# ProgrammersKeyboard_Keyboard_Schematic.net
KiCad netlist of a schematic drawn in EAGLE
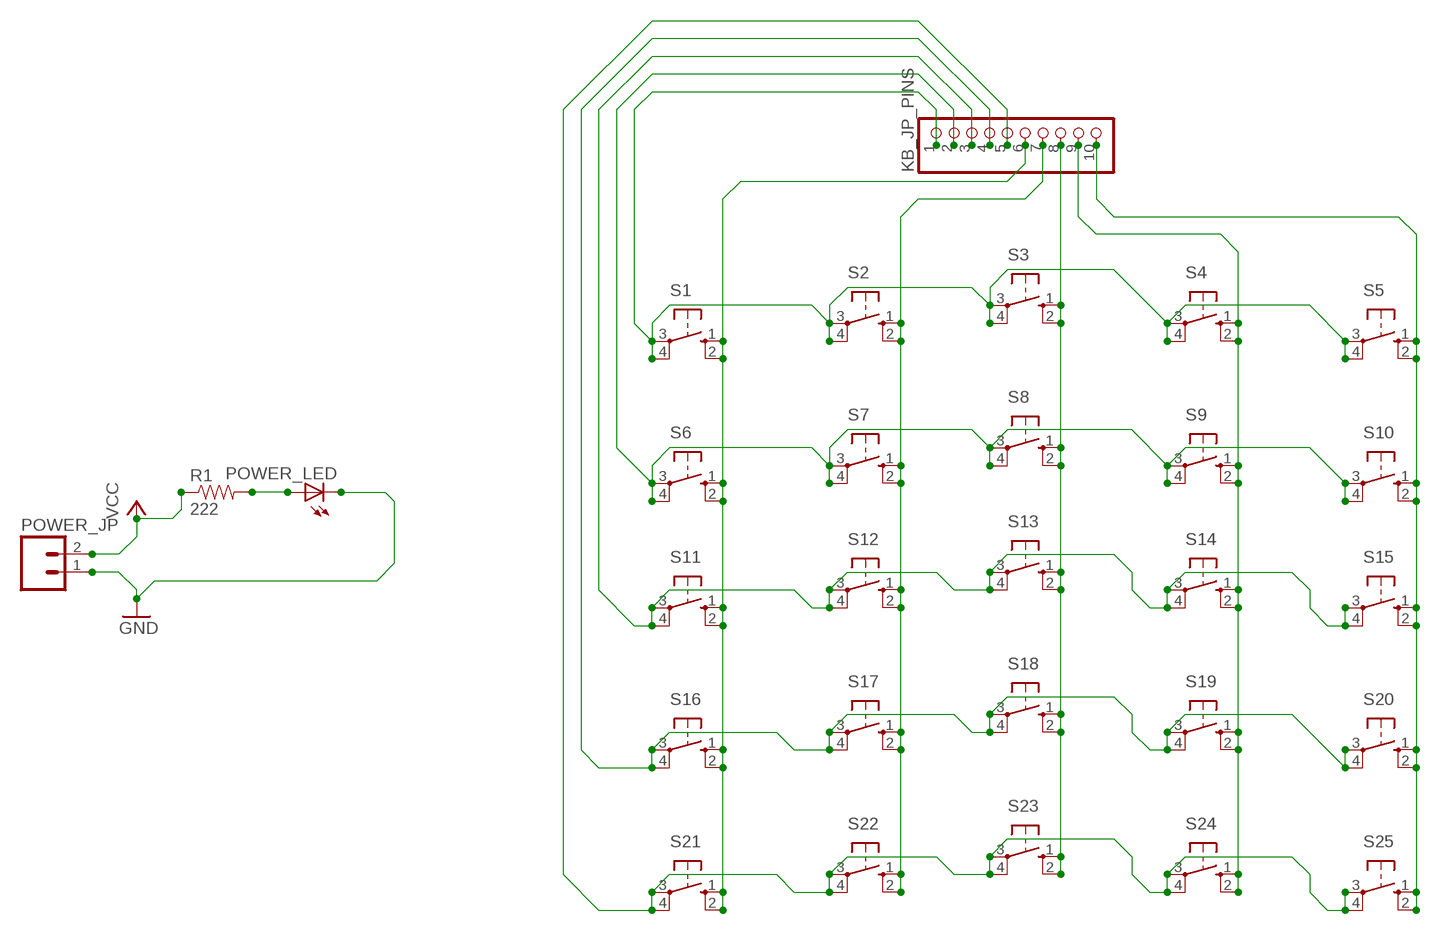
[diagram p0: schematic, sheet 1]

(export (version "E")
  (design (tool "Eeschema 10.0.6"))
  (components
    (comp (ref "KB_JP_PINS")
      (value "PINHD-1X10/90")
      (footprint "eagle-import:1X10_90")
      (libsource (lib "eagle-import") (part "PINHD-1X10/90"))
    )
    (comp (ref "POWER_JP")
      (value "M02PTH3")
      (footprint "eagle-import:1X02_LONGPADS")
      (libsource (lib "eagle-import") (part "M02PTH3"))
    )
    (comp (ref "POWER_LED")
      (value "LEDSMT1206")
      (footprint "eagle-import:1206")
      (libsource (lib "eagle-import") (part "LEDSMT1206"))
    )
    (comp (ref "R1")
      (value "222")
      (footprint "eagle-import:1206")
      (libsource (lib "eagle-import") (part "RESISTOR1206"))
    )
    (comp (ref "S1")
      (value "10-XX")
      (footprint "eagle-import:B3F-10XX")
      (fields (field (name "MPN") "B3F-1000"))
      (libsource (lib "eagle-import") (part "10-XX"))
    )
    (comp (ref "S2")
      (value "10-XX")
      (footprint "eagle-import:B3F-10XX")
      (fields (field (name "MPN") "B3F-1000"))
      (libsource (lib "eagle-import") (part "10-XX"))
    )
    (comp (ref "S3")
      (value "10-XX")
      (footprint "eagle-import:B3F-10XX")
      (fields (field (name "MPN") "B3F-1000"))
      (libsource (lib "eagle-import") (part "10-XX"))
    )
    (comp (ref "S4")
      (value "10-XX")
      (footprint "eagle-import:B3F-10XX")
      (fields (field (name "MPN") "B3F-1000"))
      (libsource (lib "eagle-import") (part "10-XX"))
    )
    (comp (ref "S5")
      (value "10-XX")
      (footprint "eagle-import:B3F-10XX")
      (fields (field (name "MPN") "B3F-1000"))
      (libsource (lib "eagle-import") (part "10-XX"))
    )
    (comp (ref "S6")
      (value "10-XX")
      (footprint "eagle-import:B3F-10XX")
      (fields (field (name "MPN") "B3F-1000"))
      (libsource (lib "eagle-import") (part "10-XX"))
    )
    (comp (ref "S7")
      (value "10-XX")
      (footprint "eagle-import:B3F-10XX")
      (fields (field (name "MPN") "B3F-1000"))
      (libsource (lib "eagle-import") (part "10-XX"))
    )
    (comp (ref "S8")
      (value "10-XX")
      (footprint "eagle-import:B3F-10XX")
      (fields (field (name "MPN") "B3F-1000"))
      (libsource (lib "eagle-import") (part "10-XX"))
    )
    (comp (ref "S9")
      (value "10-XX")
      (footprint "eagle-import:B3F-10XX")
      (fields (field (name "MPN") "B3F-1000"))
      (libsource (lib "eagle-import") (part "10-XX"))
    )
    (comp (ref "S10")
      (value "10-XX")
      (footprint "eagle-import:B3F-10XX")
      (fields (field (name "MPN") "B3F-1000"))
      (libsource (lib "eagle-import") (part "10-XX"))
    )
    (comp (ref "S11")
      (value "10-XX")
      (footprint "eagle-import:B3F-10XX")
      (fields (field (name "MPN") "B3F-1000"))
      (libsource (lib "eagle-import") (part "10-XX"))
    )
    (comp (ref "S12")
      (value "10-XX")
      (footprint "eagle-import:B3F-10XX")
      (fields (field (name "MPN") "B3F-1000"))
      (libsource (lib "eagle-import") (part "10-XX"))
    )
    (comp (ref "S13")
      (value "10-XX")
      (footprint "eagle-import:B3F-10XX")
      (fields (field (name "MPN") "B3F-1000"))
      (libsource (lib "eagle-import") (part "10-XX"))
    )
    (comp (ref "S14")
      (value "10-XX")
      (footprint "eagle-import:B3F-10XX")
      (fields (field (name "MPN") "B3F-1000"))
      (libsource (lib "eagle-import") (part "10-XX"))
    )
    (comp (ref "S15")
      (value "10-XX")
      (footprint "eagle-import:B3F-10XX")
      (fields (field (name "MPN") "B3F-1000"))
      (libsource (lib "eagle-import") (part "10-XX"))
    )
    (comp (ref "S16")
      (value "10-XX")
      (footprint "eagle-import:B3F-10XX")
      (fields (field (name "MPN") "B3F-1000"))
      (libsource (lib "eagle-import") (part "10-XX"))
    )
    (comp (ref "S17")
      (value "10-XX")
      (footprint "eagle-import:B3F-10XX")
      (fields (field (name "MPN") "B3F-1000"))
      (libsource (lib "eagle-import") (part "10-XX"))
    )
    (comp (ref "S18")
      (value "10-XX")
      (footprint "eagle-import:B3F-10XX")
      (fields (field (name "MPN") "B3F-1000"))
      (libsource (lib "eagle-import") (part "10-XX"))
    )
    (comp (ref "S19")
      (value "10-XX")
      (footprint "eagle-import:B3F-10XX")
      (fields (field (name "MPN") "B3F-1000"))
      (libsource (lib "eagle-import") (part "10-XX"))
    )
    (comp (ref "S20")
      (value "10-XX")
      (footprint "eagle-import:B3F-10XX")
      (fields (field (name "MPN") "B3F-1000"))
      (libsource (lib "eagle-import") (part "10-XX"))
    )
    (comp (ref "S21")
      (value "10-XX")
      (footprint "eagle-import:B3F-10XX")
      (fields (field (name "MPN") "B3F-1000"))
      (libsource (lib "eagle-import") (part "10-XX"))
    )
    (comp (ref "S22")
      (value "10-XX")
      (footprint "eagle-import:B3F-10XX")
      (fields (field (name "MPN") "B3F-1000"))
      (libsource (lib "eagle-import") (part "10-XX"))
    )
    (comp (ref "S23")
      (value "10-XX")
      (footprint "eagle-import:B3F-10XX")
      (fields (field (name "MPN") "B3F-1000"))
      (libsource (lib "eagle-import") (part "10-XX"))
    )
    (comp (ref "S24")
      (value "10-XX")
      (footprint "eagle-import:B3F-10XX")
      (fields (field (name "MPN") "B3F-1000"))
      (libsource (lib "eagle-import") (part "10-XX"))
    )
    (comp (ref "S25")
      (value "10-XX")
      (footprint "eagle-import:B3F-10XX")
      (fields (field (name "MPN") "B3F-1000"))
      (libsource (lib "eagle-import") (part "10-XX"))
    )
  )
  (nets
    (net (code "1") (name "GND") (class "Default")
      (node (ref "POWER_JP") (pin "1") (pinfunction "1_1") (pintype "passive"))
      (node (ref "POWER_LED") (pin "C") (pinfunction "C_C") (pintype "passive"))
    )
    (net (code "2") (name "Net-(POWER_LED-PadA)") (class "Default")
      (node (ref "POWER_LED") (pin "A") (pinfunction "A_A") (pintype "passive"))
      (node (ref "R1") (pin "2") (pinfunction "2_2") (pintype "passive"))
    )
    (net (code "3") (name "Net-(S1-P)") (class "Default")
      (node (ref "KB_JP_PINS") (pin "1") (pinfunction "1_1") (pintype "passive"))
      (node (ref "S1") (pin "3") (pinfunction "P_3") (pintype "passive"))
      (node (ref "S1") (pin "4") (pinfunction "P1_4") (pintype "passive"))
      (node (ref "S2") (pin "3") (pinfunction "P_3") (pintype "passive"))
      (node (ref "S2") (pin "4") (pinfunction "P1_4") (pintype "passive"))
      (node (ref "S3") (pin "3") (pinfunction "P_3") (pintype "passive"))
      (node (ref "S3") (pin "4") (pinfunction "P1_4") (pintype "passive"))
      (node (ref "S4") (pin "3") (pinfunction "P_3") (pintype "passive"))
      (node (ref "S4") (pin "4") (pinfunction "P1_4") (pintype "passive"))
      (node (ref "S5") (pin "3") (pinfunction "P_3") (pintype "passive"))
      (node (ref "S5") (pin "4") (pinfunction "P1_4") (pintype "passive"))
    )
    (net (code "4") (name "Net-(S1-S)") (class "Default")
      (node (ref "KB_JP_PINS") (pin "6") (pinfunction "6_6") (pintype "passive"))
      (node (ref "S1") (pin "1") (pinfunction "S_1") (pintype "passive"))
      (node (ref "S1") (pin "2") (pinfunction "S1_2") (pintype "passive"))
      (node (ref "S11") (pin "1") (pinfunction "S_1") (pintype "passive"))
      (node (ref "S11") (pin "2") (pinfunction "S1_2") (pintype "passive"))
      (node (ref "S16") (pin "1") (pinfunction "S_1") (pintype "passive"))
      (node (ref "S16") (pin "2") (pinfunction "S1_2") (pintype "passive"))
      (node (ref "S21") (pin "1") (pinfunction "S_1") (pintype "passive"))
      (node (ref "S21") (pin "2") (pinfunction "S1_2") (pintype "passive"))
      (node (ref "S6") (pin "1") (pinfunction "S_1") (pintype "passive"))
      (node (ref "S6") (pin "2") (pinfunction "S1_2") (pintype "passive"))
    )
    (net (code "5") (name "Net-(S10-P)") (class "Default")
      (node (ref "KB_JP_PINS") (pin "2") (pinfunction "2_2") (pintype "passive"))
      (node (ref "S10") (pin "3") (pinfunction "P_3") (pintype "passive"))
      (node (ref "S10") (pin "4") (pinfunction "P1_4") (pintype "passive"))
      (node (ref "S6") (pin "3") (pinfunction "P_3") (pintype "passive"))
      (node (ref "S6") (pin "4") (pinfunction "P1_4") (pintype "passive"))
      (node (ref "S7") (pin "3") (pinfunction "P_3") (pintype "passive"))
      (node (ref "S7") (pin "4") (pinfunction "P1_4") (pintype "passive"))
      (node (ref "S8") (pin "3") (pinfunction "P_3") (pintype "passive"))
      (node (ref "S8") (pin "4") (pinfunction "P1_4") (pintype "passive"))
      (node (ref "S9") (pin "3") (pinfunction "P_3") (pintype "passive"))
      (node (ref "S9") (pin "4") (pinfunction "P1_4") (pintype "passive"))
    )
    (net (code "6") (name "Net-(S10-S)") (class "Default")
      (node (ref "KB_JP_PINS") (pin "10") (pinfunction "10_10") (pintype "passive"))
      (node (ref "S10") (pin "1") (pinfunction "S_1") (pintype "passive"))
      (node (ref "S10") (pin "2") (pinfunction "S1_2") (pintype "passive"))
      (node (ref "S15") (pin "1") (pinfunction "S_1") (pintype "passive"))
      (node (ref "S15") (pin "2") (pinfunction "S1_2") (pintype "passive"))
      (node (ref "S20") (pin "1") (pinfunction "S_1") (pintype "passive"))
      (node (ref "S20") (pin "2") (pinfunction "S1_2") (pintype "passive"))
      (node (ref "S25") (pin "1") (pinfunction "S_1") (pintype "passive"))
      (node (ref "S25") (pin "2") (pinfunction "S1_2") (pintype "passive"))
      (node (ref "S5") (pin "1") (pinfunction "S_1") (pintype "passive"))
      (node (ref "S5") (pin "2") (pinfunction "S1_2") (pintype "passive"))
    )
    (net (code "7") (name "Net-(S11-P)") (class "Default")
      (node (ref "KB_JP_PINS") (pin "3") (pinfunction "3_3") (pintype "passive"))
      (node (ref "S11") (pin "3") (pinfunction "P_3") (pintype "passive"))
      (node (ref "S11") (pin "4") (pinfunction "P1_4") (pintype "passive"))
      (node (ref "S12") (pin "3") (pinfunction "P_3") (pintype "passive"))
      (node (ref "S12") (pin "4") (pinfunction "P1_4") (pintype "passive"))
      (node (ref "S13") (pin "3") (pinfunction "P_3") (pintype "passive"))
      (node (ref "S13") (pin "4") (pinfunction "P1_4") (pintype "passive"))
      (node (ref "S14") (pin "3") (pinfunction "P_3") (pintype "passive"))
      (node (ref "S14") (pin "4") (pinfunction "P1_4") (pintype "passive"))
      (node (ref "S15") (pin "3") (pinfunction "P_3") (pintype "passive"))
      (node (ref "S15") (pin "4") (pinfunction "P1_4") (pintype "passive"))
    )
    (net (code "8") (name "Net-(S12-S)") (class "Default")
      (node (ref "KB_JP_PINS") (pin "7") (pinfunction "7_7") (pintype "passive"))
      (node (ref "S12") (pin "1") (pinfunction "S_1") (pintype "passive"))
      (node (ref "S12") (pin "2") (pinfunction "S1_2") (pintype "passive"))
      (node (ref "S17") (pin "1") (pinfunction "S_1") (pintype "passive"))
      (node (ref "S17") (pin "2") (pinfunction "S1_2") (pintype "passive"))
      (node (ref "S2") (pin "1") (pinfunction "S_1") (pintype "passive"))
      (node (ref "S2") (pin "2") (pinfunction "S1_2") (pintype "passive"))
      (node (ref "S22") (pin "1") (pinfunction "S_1") (pintype "passive"))
      (node (ref "S22") (pin "2") (pinfunction "S1_2") (pintype "passive"))
      (node (ref "S7") (pin "1") (pinfunction "S_1") (pintype "passive"))
      (node (ref "S7") (pin "2") (pinfunction "S1_2") (pintype "passive"))
    )
    (net (code "9") (name "Net-(S13-S)") (class "Default")
      (node (ref "KB_JP_PINS") (pin "8") (pinfunction "8_8") (pintype "passive"))
      (node (ref "S13") (pin "1") (pinfunction "S_1") (pintype "passive"))
      (node (ref "S13") (pin "2") (pinfunction "S1_2") (pintype "passive"))
      (node (ref "S18") (pin "1") (pinfunction "S_1") (pintype "passive"))
      (node (ref "S18") (pin "2") (pinfunction "S1_2") (pintype "passive"))
      (node (ref "S23") (pin "1") (pinfunction "S_1") (pintype "passive"))
      (node (ref "S23") (pin "2") (pinfunction "S1_2") (pintype "passive"))
      (node (ref "S3") (pin "1") (pinfunction "S_1") (pintype "passive"))
      (node (ref "S3") (pin "2") (pinfunction "S1_2") (pintype "passive"))
      (node (ref "S8") (pin "1") (pinfunction "S_1") (pintype "passive"))
      (node (ref "S8") (pin "2") (pinfunction "S1_2") (pintype "passive"))
    )
    (net (code "10") (name "Net-(S14-S)") (class "Default")
      (node (ref "KB_JP_PINS") (pin "9") (pinfunction "9_9") (pintype "passive"))
      (node (ref "S14") (pin "1") (pinfunction "S_1") (pintype "passive"))
      (node (ref "S14") (pin "2") (pinfunction "S1_2") (pintype "passive"))
      (node (ref "S19") (pin "1") (pinfunction "S_1") (pintype "passive"))
      (node (ref "S19") (pin "2") (pinfunction "S1_2") (pintype "passive"))
      (node (ref "S24") (pin "1") (pinfunction "S_1") (pintype "passive"))
      (node (ref "S24") (pin "2") (pinfunction "S1_2") (pintype "passive"))
      (node (ref "S4") (pin "1") (pinfunction "S_1") (pintype "passive"))
      (node (ref "S4") (pin "2") (pinfunction "S1_2") (pintype "passive"))
      (node (ref "S9") (pin "1") (pinfunction "S_1") (pintype "passive"))
      (node (ref "S9") (pin "2") (pinfunction "S1_2") (pintype "passive"))
    )
    (net (code "11") (name "Net-(S16-P)") (class "Default")
      (node (ref "KB_JP_PINS") (pin "4") (pinfunction "4_4") (pintype "passive"))
      (node (ref "S16") (pin "3") (pinfunction "P_3") (pintype "passive"))
      (node (ref "S16") (pin "4") (pinfunction "P1_4") (pintype "passive"))
      (node (ref "S17") (pin "3") (pinfunction "P_3") (pintype "passive"))
      (node (ref "S17") (pin "4") (pinfunction "P1_4") (pintype "passive"))
      (node (ref "S18") (pin "3") (pinfunction "P_3") (pintype "passive"))
      (node (ref "S18") (pin "4") (pinfunction "P1_4") (pintype "passive"))
      (node (ref "S19") (pin "3") (pinfunction "P_3") (pintype "passive"))
      (node (ref "S19") (pin "4") (pinfunction "P1_4") (pintype "passive"))
      (node (ref "S20") (pin "3") (pinfunction "P_3") (pintype "passive"))
      (node (ref "S20") (pin "4") (pinfunction "P1_4") (pintype "passive"))
    )
    (net (code "12") (name "Net-(S21-P)") (class "Default")
      (node (ref "KB_JP_PINS") (pin "5") (pinfunction "5_5") (pintype "passive"))
      (node (ref "S21") (pin "3") (pinfunction "P_3") (pintype "passive"))
      (node (ref "S21") (pin "4") (pinfunction "P1_4") (pintype "passive"))
      (node (ref "S22") (pin "3") (pinfunction "P_3") (pintype "passive"))
      (node (ref "S22") (pin "4") (pinfunction "P1_4") (pintype "passive"))
      (node (ref "S23") (pin "3") (pinfunction "P_3") (pintype "passive"))
      (node (ref "S23") (pin "4") (pinfunction "P1_4") (pintype "passive"))
      (node (ref "S24") (pin "3") (pinfunction "P_3") (pintype "passive"))
      (node (ref "S24") (pin "4") (pinfunction "P1_4") (pintype "passive"))
      (node (ref "S25") (pin "3") (pinfunction "P_3") (pintype "passive"))
      (node (ref "S25") (pin "4") (pinfunction "P1_4") (pintype "passive"))
    )
    (net (code "13") (name "VCC") (class "Default")
      (node (ref "POWER_JP") (pin "2") (pinfunction "2_2") (pintype "passive"))
      (node (ref "R1") (pin "1") (pinfunction "1_1") (pintype "passive"))
    )
  )
)
